# BME280_Daughter.net
KiCad netlist of a schematic drawn in EAGLE
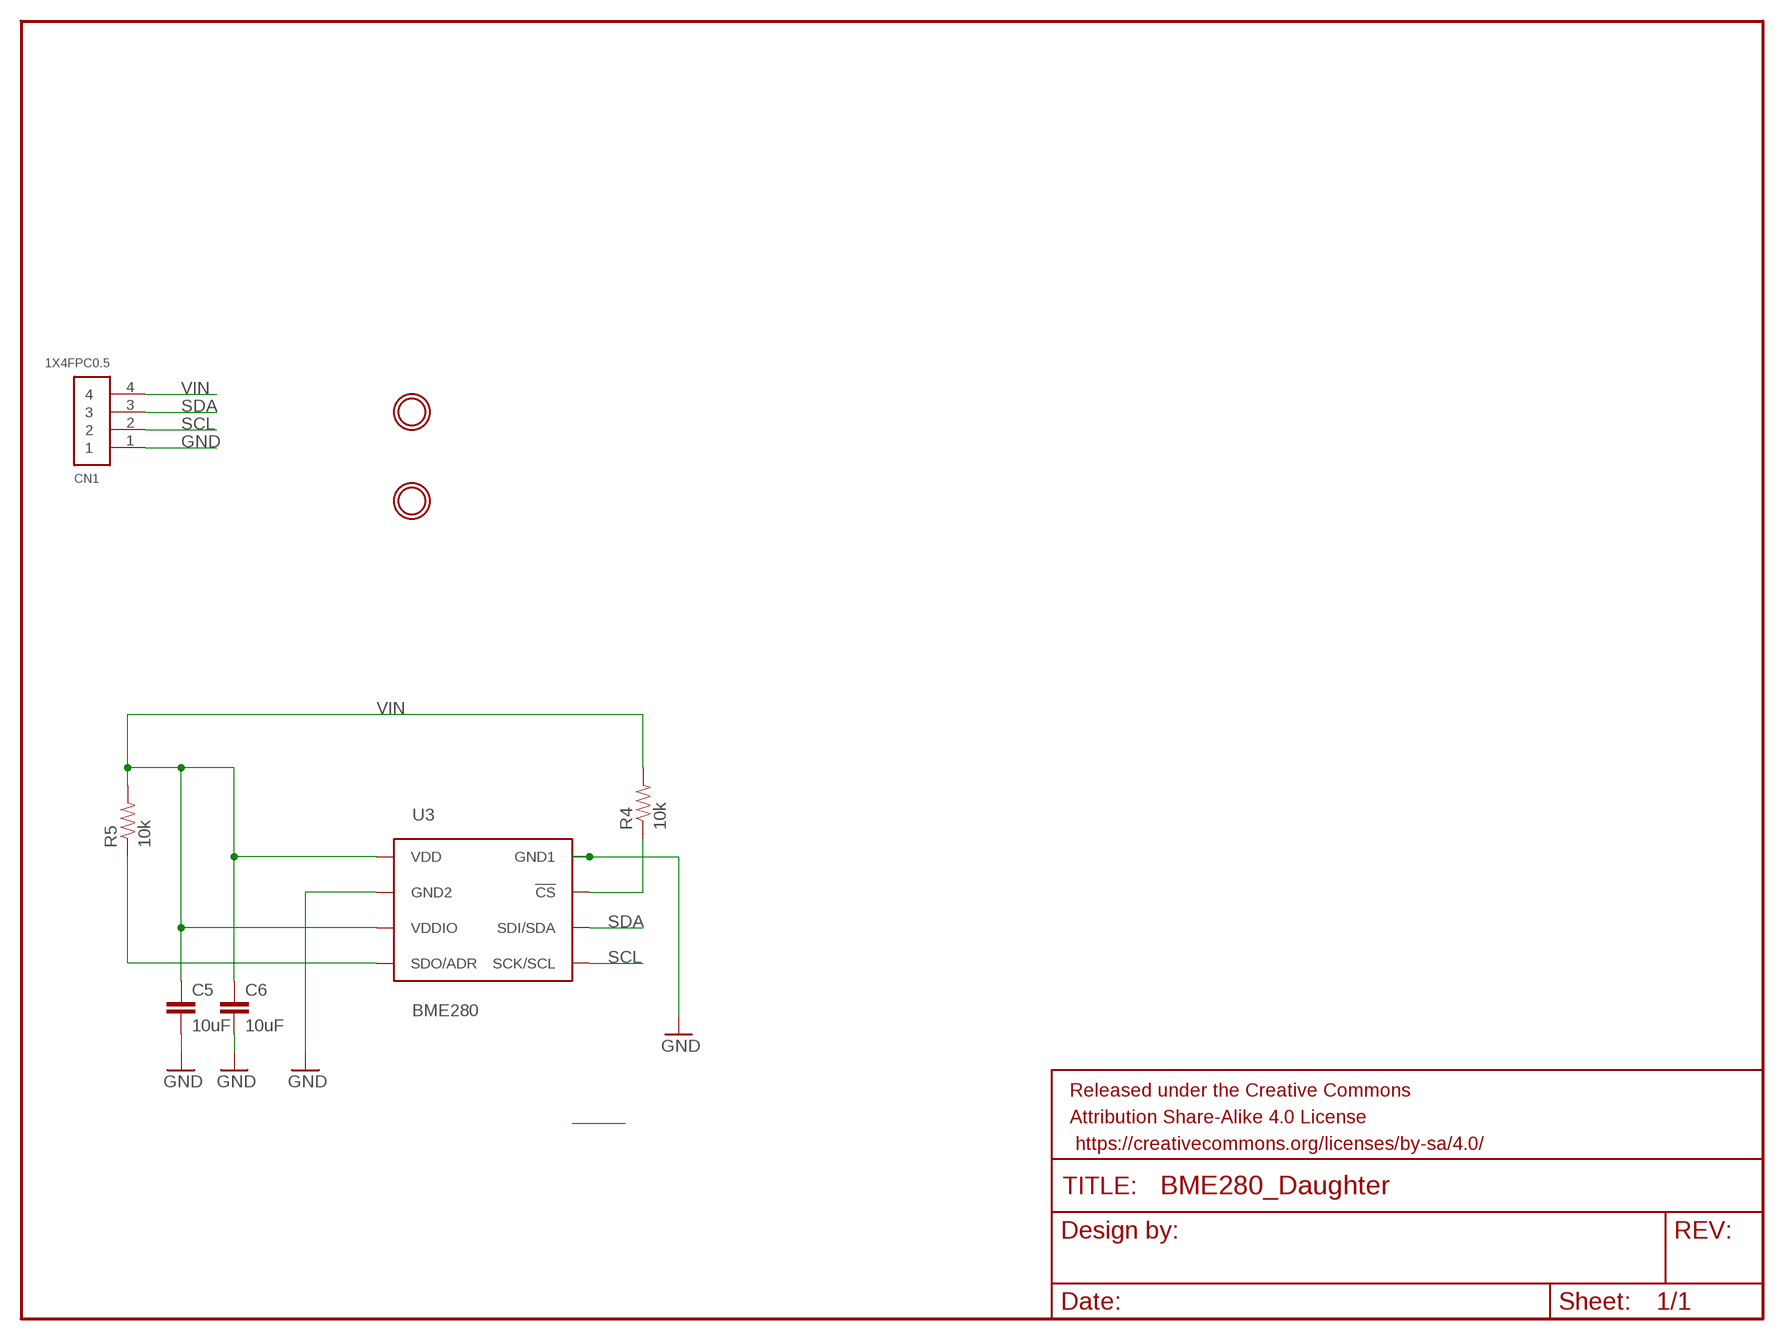
[diagram p0: schematic, sheet 1]

(export (version "E")
  (design (tool "Eeschema 10.0.6"))
  (components
    (comp (ref "C5")
      (value "10uF")
      (footprint "eagle-import:0805")
      (libsource (lib "eagle-import") (part "CAP0805"))
    )
    (comp (ref "C6")
      (value "10uF")
      (footprint "eagle-import:0805")
      (libsource (lib "eagle-import") (part "CAP0805"))
    )
    (comp (ref "CN1")
      (value "1X4FPC0.5")
      (footprint "eagle-import:FPC_0.5MM-4")
      (libsource (lib "eagle-import") (part "1X4FPC0.5"))
    )
    (comp (ref "FRAME1")
      (value "FRAME-LETTER")
      (footprint "eagle-import:CREATIVE_COMMONS")
      (libsource (lib "eagle-import") (part "FRAME-LETTER"))
    )
    (comp (ref "R4")
      (value "10k")
      (footprint "eagle-import:0805")
      (libsource (lib "eagle-import") (part "RESISTOR0805-RES"))
    )
    (comp (ref "R5")
      (value "10k")
      (footprint "eagle-import:0805")
      (libsource (lib "eagle-import") (part "RESISTOR0805-RES"))
    )
    (comp (ref "U$1")
      (value "MOUNTINGHOLE2.0")
      (footprint "eagle-import:MOUNTINGHOLE_2.0_PLATED")
      (libsource (lib "eagle-import") (part "MOUNTINGHOLE2.0"))
    )
    (comp (ref "U$2")
      (value "MOUNTINGHOLE2.0")
      (footprint "eagle-import:MOUNTINGHOLE_2.0_PLATED")
      (libsource (lib "eagle-import") (part "MOUNTINGHOLE2.0"))
    )
    (comp (ref "U3")
      (value "BME280")
      (footprint "eagle-import:BME280_LGA")
      (libsource (lib "eagle-import") (part "BME280"))
    )
  )
  (nets
    (net (code "1") (name "/SCL") (class "Default")
      (node (ref "CN1") (pin "2") (pinfunction "2_2") (pintype "bidirectional"))
      (node (ref "U3") (pin "P$4") (pinfunction "SCK/SCL_P$4") (pintype "bidirectional"))
    )
    (net (code "2") (name "/SDA") (class "Default")
      (node (ref "CN1") (pin "3") (pinfunction "3_3") (pintype "bidirectional"))
      (node (ref "U3") (pin "P$3") (pinfunction "SDI/SDA_P$3") (pintype "bidirectional"))
    )
    (net (code "3") (name "/VIN") (class "Default")
      (node (ref "C5") (pin "1") (pinfunction "1_1") (pintype "passive"))
      (node (ref "C6") (pin "1") (pinfunction "1_1") (pintype "passive"))
      (node (ref "CN1") (pin "4") (pinfunction "4_4") (pintype "bidirectional"))
      (node (ref "R4") (pin "2") (pinfunction "2_2") (pintype "passive"))
      (node (ref "R5") (pin "2") (pinfunction "2_2") (pintype "passive"))
      (node (ref "U3") (pin "P$6") (pinfunction "VDDIO_P$6") (pintype "bidirectional"))
      (node (ref "U3") (pin "P$8") (pinfunction "VDD_P$8") (pintype "bidirectional"))
    )
    (net (code "4") (name "GND") (class "Default")
      (node (ref "C5") (pin "2") (pinfunction "2_2") (pintype "passive"))
      (node (ref "C6") (pin "2") (pinfunction "2_2") (pintype "passive"))
      (node (ref "CN1") (pin "1") (pinfunction "1_1") (pintype "bidirectional"))
      (node (ref "U3") (pin "P$1") (pinfunction "GND1_P$1") (pintype "bidirectional"))
      (node (ref "U3") (pin "P$7") (pinfunction "GND2_P$7") (pintype "bidirectional"))
    )
    (net (code "5") (name "Net-(U3-SDO{slash}ADR)") (class "Default")
      (node (ref "R5") (pin "1") (pinfunction "1_1") (pintype "passive"))
      (node (ref "U3") (pin "P$5") (pinfunction "SDO/ADR_P$5") (pintype "bidirectional"))
    )
    (net (code "6") (name "Net-(U3-~{CS})") (class "Default")
      (node (ref "R4") (pin "1") (pinfunction "1_1") (pintype "passive"))
      (node (ref "U3") (pin "P$2") (pinfunction "~{CS}_P$2") (pintype "bidirectional"))
    )
  )
)
